# BuckConvertor.net
KiCad netlist of a schematic drawn in EAGLE
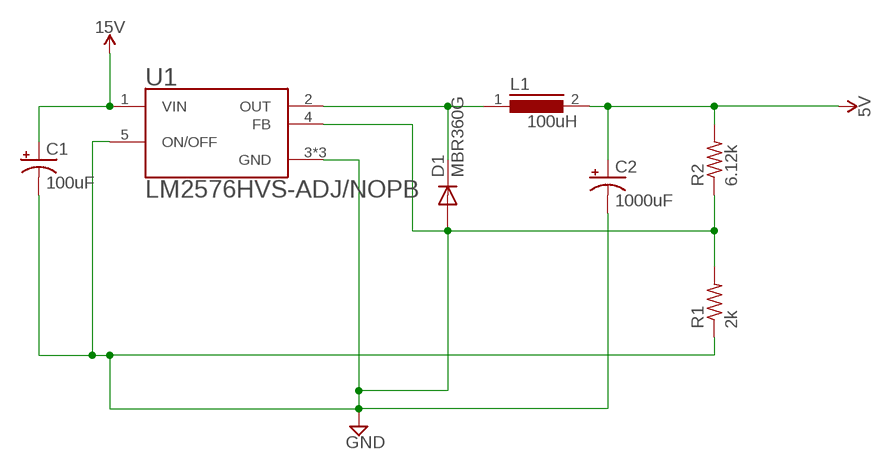
[diagram p0: schematic, sheet 1]

(export (version "E")
  (design (tool "Eeschema 10.0.6"))
  (components
    (comp (ref "C1")
      (value "100uF")
      (footprint "eagle-import:CPOL-RADIAL-5MM-10MM")
      (libsource (lib "eagle-import") (part "1000UF-RADIAL-5MM-25V-20%"))
    )
    (comp (ref "C2")
      (value "1000uF")
      (footprint "eagle-import:CPOL-RADIAL-5MM-10MM")
      (libsource (lib "eagle-import") (part "1000UF-RADIAL-5MM-25V-20%"))
    )
    (comp (ref "D1")
      (value "MBR360G")
      (footprint "eagle-import:DIOB_MBR360G")
      (fields (field (name "MF") "ON Semiconductor"))
      (libsource (lib "eagle-import") (part "MBR360G"))
    )
    (comp (ref "L1")
      (value "100uH")
      (footprint "eagle-import:DR73")
      (libsource (lib "eagle-import") (part "DR73"))
    )
    (comp (ref "R1")
      (value "2k")
      (footprint "eagle-import:0204_5")
      (libsource (lib "eagle-import") (part "R-US_0204/5"))
    )
    (comp (ref "R2")
      (value "6.12k")
      (footprint "eagle-import:0204_5")
      (libsource (lib "eagle-import") (part "R-US_0204/5"))
    )
    (comp (ref "U1")
      (value "LM2576HVS-ADJ/NOPB")
      (footprint "eagle-import:REG_LM2576HVS-ADJ_NOPB")
      (fields (field (name "MF") "Texas Instruments"))
      (libsource (lib "eagle-import") (part "LM2576HVS-ADJ/NOPB"))
    )
  )
  (nets
    (net (code "1") (name "5V") (class "Default")
      (node (ref "C2") (pin "+") (pinfunction "+_+") (pintype "passive"))
      (node (ref "L1") (pin "2") (pinfunction "2_2") (pintype "passive"))
      (node (ref "R2") (pin "2") (pinfunction "2_2") (pintype "passive"))
    )
    (net (code "2") (name "15V") (class "Default")
      (node (ref "C1") (pin "+") (pinfunction "+_+") (pintype "passive"))
      (node (ref "U1") (pin "1") (pinfunction "VIN_1") (pintype "input"))
    )
    (net (code "3") (name "GND") (class "Default")
      (node (ref "C1") (pin "-") (pinfunction "-_-") (pintype "passive"))
      (node (ref "C2") (pin "-") (pinfunction "-_-") (pintype "passive"))
      (node (ref "D1") (pin "A") (pinfunction "A_A") (pintype "passive"))
      (node (ref "R1") (pin "1") (pinfunction "1_1") (pintype "passive"))
      (node (ref "R1") (pin "2") (pinfunction "2_2") (pintype "passive"))
      (node (ref "R2") (pin "1") (pinfunction "1_1") (pintype "passive"))
      (node (ref "U1") (pin "3") (pinfunction "GND_3") (pintype "power_in"))
      (node (ref "U1") (pin "4") (pinfunction "FB_4") (pintype "passive"))
      (node (ref "U1") (pin "5") (pinfunction "ON/OFF_5") (pintype "input"))
      (node (ref "U1") (pin "6") (pinfunction "GND_6") (pintype "power_in"))
      (node (ref "U1") (pin "7") (pinfunction "GND_7") (pintype "power_in"))
    )
    (net (code "4") (name "Net-(U1-OUT)") (class "Default")
      (node (ref "D1") (pin "C") (pinfunction "C_C") (pintype "passive"))
      (node (ref "L1") (pin "1") (pinfunction "1_1") (pintype "passive"))
      (node (ref "U1") (pin "2") (pinfunction "OUT_2") (pintype "output"))
    )
  )
)
